# XBee_Shield_v2_0b.net
KiCad netlist of a schematic drawn in EAGLE
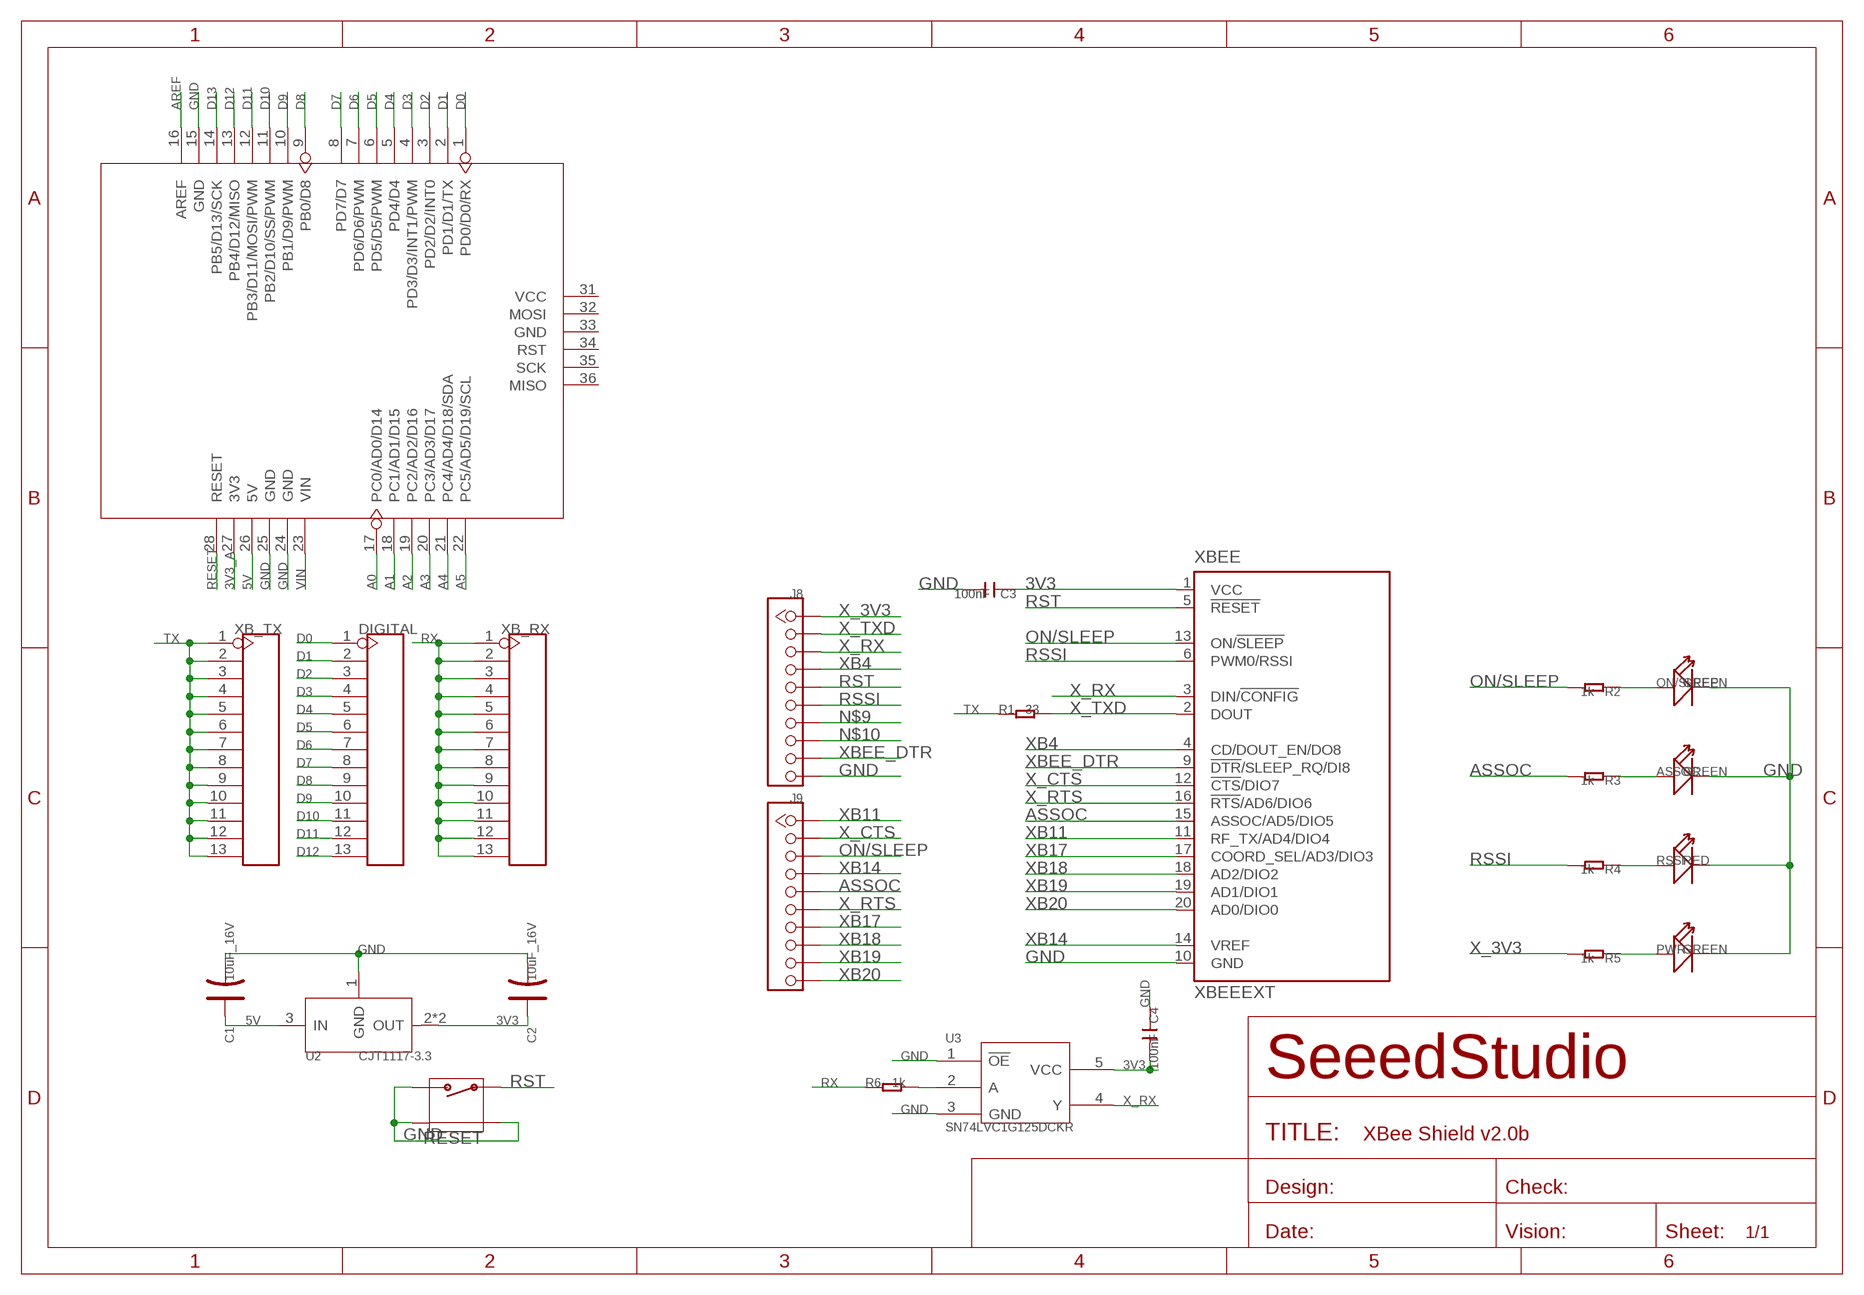
[diagram p0: schematic, sheet 1]

(export (version "E")
  (design (tool "Eeschema 10.0.6"))
  (components
    (comp (ref "ASSOC")
      (value "GREEN")
      (footprint "eagle-import:LED-0603")
      (libsource (lib "eagle-import") (part "LED'0603'"))
    )
    (comp (ref "C1")
      (value "10uF_16V")
      (footprint "eagle-import:AVX-A")
      (libsource (lib "eagle-import") (part "CAP-AVX-A"))
    )
    (comp (ref "C2")
      (value "10uF_16V")
      (footprint "eagle-import:AVX-A")
      (libsource (lib "eagle-import") (part "CAP-AVX-A"))
    )
    (comp (ref "C3")
      (value "100nF")
      (footprint "eagle-import:C0603")
      (libsource (lib "eagle-import") (part "C-0603"))
    )
    (comp (ref "C4")
      (value "100nF")
      (footprint "eagle-import:C0603")
      (libsource (lib "eagle-import") (part "C-0603"))
    )
    (comp (ref "DIGITAL")
      (value "HEADER-13P")
      (footprint "eagle-import:13P-2.54")
      (libsource (lib "eagle-import") (part "HEADER-13P"))
    )
    (comp (ref "J8")
      (value "DNP")
      (footprint "eagle-import:CK1X10")
      (libsource (lib "eagle-import") (part "CK1X10DD"))
    )
    (comp (ref "J9")
      (value "DNP")
      (footprint "eagle-import:CK1X10")
      (libsource (lib "eagle-import") (part "CK1X10DD"))
    )
    (comp (ref "ON/SLEEP")
      (value "GREEN")
      (footprint "eagle-import:LED-0603")
      (libsource (lib "eagle-import") (part "LED'0603'"))
    )
    (comp (ref "PWR")
      (value "GREEN")
      (footprint "eagle-import:LED-0603")
      (libsource (lib "eagle-import") (part "LED'0603'"))
    )
    (comp (ref "R1")
      (value "33")
      (footprint "eagle-import:R0603")
      (libsource (lib "eagle-import") (part "R-0603"))
    )
    (comp (ref "R2")
      (value "1k")
      (footprint "eagle-import:R0603")
      (libsource (lib "eagle-import") (part "R-0603"))
    )
    (comp (ref "R3")
      (value "1k")
      (footprint "eagle-import:R0603")
      (libsource (lib "eagle-import") (part "R-0603"))
    )
    (comp (ref "R4")
      (value "1k")
      (footprint "eagle-import:R0603")
      (libsource (lib "eagle-import") (part "R-0603"))
    )
    (comp (ref "R5")
      (value "1k")
      (footprint "eagle-import:R0603")
      (libsource (lib "eagle-import") (part "R-0603"))
    )
    (comp (ref "R6")
      (value "1k")
      (footprint "eagle-import:R0603")
      (libsource (lib "eagle-import") (part "R-0603"))
    )
    (comp (ref "RESET")
      (value "FOR_TEST_ALBERT_V6_BUTTON_4P_SMD")
      (footprint "eagle-import:FOR_TEST_ALBERT_V6_4P-SMD-7X3.5X3.5")
      (libsource (lib "eagle-import") (part "FOR_TEST_ALBERT_V6_BUTTON_4P_SMD"))
    )
    (comp (ref "RSSI")
      (value "RED")
      (footprint "eagle-import:LED-0603")
      (libsource (lib "eagle-import") (part "LED'0603'"))
    )
    (comp (ref "U1")
      (value "ARDUINO'W/O-SILK'")
      (footprint "eagle-import:ARDUINO-W_O-SILK")
      (libsource (lib "eagle-import") (part "ARDUINO'W/O-SILK'"))
    )
    (comp (ref "U2")
      (value "CJT1117-3.3")
      (footprint "eagle-import:SOT-223")
      (libsource (lib "eagle-import") (part "LD1117S"))
    )
    (comp (ref "U3")
      (value "SN74LVC1G125DCKR")
      (footprint "eagle-import:SOT353")
      (libsource (lib "eagle-import") (part "SN74LVC1G125DCKR"))
    )
    (comp (ref "XBEE")
      (value "XBEEEXT")
      (footprint "eagle-import:XBEE_PLUG")
      (libsource (lib "eagle-import") (part "XBEEEXT"))
    )
    (comp (ref "XB_RX")
      (value "HEADER-13P")
      (footprint "eagle-import:13P-2.54")
      (libsource (lib "eagle-import") (part "HEADER-13P"))
    )
    (comp (ref "XB_TX")
      (value "HEADER-13P")
      (footprint "eagle-import:13P-2.54")
      (libsource (lib "eagle-import") (part "HEADER-13P"))
    )
  )
  (nets
    (net (code "1") (name "/3V3") (class "Default")
      (node (ref "C2") (pin "+") (pinfunction "+_+") (pintype "passive"))
      (node (ref "C3") (pin "1") (pinfunction "1_1") (pintype "passive"))
      (node (ref "C4") (pin "2") (pinfunction "2_2") (pintype "passive"))
      (node (ref "U2") (pin "2") (pinfunction "OUT_2") (pintype "bidirectional"))
      (node (ref "U2") (pin "TER") (pinfunction "OUT_TER") (pintype "bidirectional"))
      (node (ref "U3") (pin "5") (pinfunction "VCC_5") (pintype "bidirectional"))
      (node (ref "XBEE") (pin "1") (pinfunction "VCC_1") (pintype "power_in"))
    )
    (net (code "2") (name "/3V3_A") (class "Default")
      (node (ref "U1") (pin "27") (pinfunction "3V3_27") (pintype "bidirectional"))
    )
    (net (code "3") (name "/5V") (class "Default")
      (node (ref "C1") (pin "+") (pinfunction "+_+") (pintype "passive"))
      (node (ref "U1") (pin "26") (pinfunction "5V_26") (pintype "bidirectional"))
      (node (ref "U2") (pin "3") (pinfunction "IN_3") (pintype "bidirectional"))
    )
    (net (code "4") (name "/A0") (class "Default")
      (node (ref "U1") (pin "17") (pinfunction "PC0/AD0/D14_17") (pintype "bidirectional"))
    )
    (net (code "5") (name "/A1") (class "Default")
      (node (ref "U1") (pin "18") (pinfunction "PC1/AD1/D15_18") (pintype "bidirectional"))
    )
    (net (code "6") (name "/A2") (class "Default")
      (node (ref "U1") (pin "19") (pinfunction "PC2/AD2/D16_19") (pintype "bidirectional"))
    )
    (net (code "7") (name "/A3") (class "Default")
      (node (ref "U1") (pin "20") (pinfunction "PC3/AD3/D17_20") (pintype "bidirectional"))
    )
    (net (code "8") (name "/A4") (class "Default")
      (node (ref "U1") (pin "21") (pinfunction "PC4/AD4/D18/SDA_21") (pintype "bidirectional"))
    )
    (net (code "9") (name "/A5") (class "Default")
      (node (ref "U1") (pin "22") (pinfunction "PC5/AD5/D19/SCL_22") (pintype "bidirectional"))
    )
    (net (code "10") (name "/AREF") (class "Default")
      (node (ref "U1") (pin "16") (pinfunction "AREF_16") (pintype "bidirectional"))
    )
    (net (code "11") (name "/ASSOC") (class "Default")
      (node (ref "J9") (pin "5") (pinfunction "5_5") (pintype "bidirectional"))
      (node (ref "R3") (pin "2") (pinfunction "2_2") (pintype "passive"))
      (node (ref "XBEE") (pin "15") (pinfunction "ASSOC/AD5/DIO5_15") (pintype "bidirectional"))
    )
    (net (code "12") (name "/D0") (class "Default")
      (node (ref "DIGITAL") (pin "1") (pinfunction "1_1") (pintype "bidirectional"))
      (node (ref "U1") (pin "1") (pinfunction "PD0/D0/RX_1") (pintype "bidirectional"))
    )
    (net (code "13") (name "/D1") (class "Default")
      (node (ref "DIGITAL") (pin "2") (pinfunction "2_2") (pintype "bidirectional"))
      (node (ref "U1") (pin "2") (pinfunction "PD1/D1/TX_2") (pintype "bidirectional"))
    )
    (net (code "14") (name "/D2") (class "Default")
      (node (ref "DIGITAL") (pin "3") (pinfunction "3_3") (pintype "bidirectional"))
      (node (ref "U1") (pin "3") (pinfunction "PD2/D2/INT0_3") (pintype "bidirectional"))
    )
    (net (code "15") (name "/D3") (class "Default")
      (node (ref "DIGITAL") (pin "4") (pinfunction "4_4") (pintype "bidirectional"))
      (node (ref "U1") (pin "4") (pinfunction "PD3/D3/INT1/PWM_4") (pintype "bidirectional"))
    )
    (net (code "16") (name "/D4") (class "Default")
      (node (ref "DIGITAL") (pin "5") (pinfunction "5_5") (pintype "bidirectional"))
      (node (ref "U1") (pin "5") (pinfunction "PD4/D4_5") (pintype "bidirectional"))
    )
    (net (code "17") (name "/D5") (class "Default")
      (node (ref "DIGITAL") (pin "6") (pinfunction "6_6") (pintype "bidirectional"))
      (node (ref "U1") (pin "6") (pinfunction "PD5/D5/PWM_6") (pintype "bidirectional"))
    )
    (net (code "18") (name "/D6") (class "Default")
      (node (ref "DIGITAL") (pin "7") (pinfunction "7_7") (pintype "bidirectional"))
      (node (ref "U1") (pin "7") (pinfunction "PD6/D6/PWM_7") (pintype "bidirectional"))
    )
    (net (code "19") (name "/D7") (class "Default")
      (node (ref "DIGITAL") (pin "8") (pinfunction "8_8") (pintype "bidirectional"))
      (node (ref "U1") (pin "8") (pinfunction "PD7/D7_8") (pintype "bidirectional"))
    )
    (net (code "20") (name "/D8") (class "Default")
      (node (ref "DIGITAL") (pin "9") (pinfunction "9_9") (pintype "bidirectional"))
      (node (ref "U1") (pin "9") (pinfunction "PB0/D8_9") (pintype "bidirectional"))
    )
    (net (code "21") (name "/D9") (class "Default")
      (node (ref "DIGITAL") (pin "10") (pinfunction "10_10") (pintype "bidirectional"))
      (node (ref "U1") (pin "10") (pinfunction "PB1/D9/PWM_10") (pintype "bidirectional"))
    )
    (net (code "22") (name "/D10") (class "Default")
      (node (ref "DIGITAL") (pin "11") (pinfunction "11_11") (pintype "bidirectional"))
      (node (ref "U1") (pin "11") (pinfunction "PB2/D10/SS/PWM_11") (pintype "bidirectional"))
    )
    (net (code "23") (name "/D11") (class "Default")
      (node (ref "DIGITAL") (pin "12") (pinfunction "12_12") (pintype "bidirectional"))
      (node (ref "U1") (pin "12") (pinfunction "PB3/D11/MOSI/PWM_12") (pintype "bidirectional"))
    )
    (net (code "24") (name "/D12") (class "Default")
      (node (ref "DIGITAL") (pin "13") (pinfunction "13_13") (pintype "bidirectional"))
      (node (ref "U1") (pin "13") (pinfunction "PB4/D12/MISO_13") (pintype "bidirectional"))
    )
    (net (code "25") (name "/D13") (class "Default")
      (node (ref "U1") (pin "14") (pinfunction "PB5/D13/SCK_14") (pintype "bidirectional"))
    )
    (net (code "26") (name "/GND") (class "Default")
      (node (ref "ASSOC") (pin "-") (pinfunction "-_-") (pintype "passive"))
      (node (ref "C1") (pin "-") (pinfunction "-_-") (pintype "passive"))
      (node (ref "C2") (pin "-") (pinfunction "-_-") (pintype "passive"))
      (node (ref "C3") (pin "2") (pinfunction "2_2") (pintype "passive"))
      (node (ref "C4") (pin "1") (pinfunction "1_1") (pintype "passive"))
      (node (ref "J8") (pin "10") (pinfunction "10_10") (pintype "bidirectional"))
      (node (ref "ON/SLEEP") (pin "-") (pinfunction "-_-") (pintype "passive"))
      (node (ref "PWR") (pin "-") (pinfunction "-_-") (pintype "passive"))
      (node (ref "RESET") (pin "2") (pinfunction "2_2") (pintype "bidirectional"))
      (node (ref "RESET") (pin "S1") (pinfunction "S1_S1") (pintype "bidirectional"))
      (node (ref "RESET") (pin "S2") (pinfunction "S2_S2") (pintype "bidirectional"))
      (node (ref "RSSI") (pin "-") (pinfunction "-_-") (pintype "passive"))
      (node (ref "U1") (pin "15") (pinfunction "GND_15") (pintype "bidirectional"))
      (node (ref "U1") (pin "24") (pinfunction "GND_24") (pintype "bidirectional"))
      (node (ref "U1") (pin "25") (pinfunction "GND_25") (pintype "bidirectional"))
      (node (ref "U2") (pin "1") (pinfunction "GND_1") (pintype "bidirectional"))
      (node (ref "U3") (pin "1") (pinfunction "~{OE}_1") (pintype "bidirectional"))
      (node (ref "U3") (pin "3") (pinfunction "GND_3") (pintype "bidirectional"))
      (node (ref "XBEE") (pin "10") (pinfunction "GND_10") (pintype "bidirectional"))
    )
    (net (code "27") (name "/N$9") (class "Default")
      (node (ref "J8") (pin "7") (pinfunction "7_7") (pintype "bidirectional"))
    )
    (net (code "28") (name "/N$10") (class "Default")
      (node (ref "J8") (pin "8") (pinfunction "8_8") (pintype "bidirectional"))
    )
    (net (code "29") (name "/ON{slash}SLEEP") (class "Default")
      (node (ref "J9") (pin "3") (pinfunction "3_3") (pintype "bidirectional"))
      (node (ref "R2") (pin "2") (pinfunction "2_2") (pintype "passive"))
      (node (ref "XBEE") (pin "13") (pinfunction "ON/~{SLEEP}_13") (pintype "output"))
    )
    (net (code "30") (name "/RESET") (class "Default")
      (node (ref "U1") (pin "28") (pinfunction "RESET_28") (pintype "bidirectional"))
    )
    (net (code "31") (name "/RSSI") (class "Default")
      (node (ref "J8") (pin "6") (pinfunction "6_6") (pintype "bidirectional"))
      (node (ref "R4") (pin "2") (pinfunction "2_2") (pintype "passive"))
      (node (ref "XBEE") (pin "6") (pinfunction "PWM0/RSSI_6") (pintype "output"))
    )
    (net (code "32") (name "/RST") (class "Default")
      (node (ref "J8") (pin "5") (pinfunction "5_5") (pintype "bidirectional"))
      (node (ref "RESET") (pin "1") (pinfunction "1_1") (pintype "bidirectional"))
      (node (ref "XBEE") (pin "5") (pinfunction "~{RESET}_5") (pintype "input"))
    )
    (net (code "33") (name "/RX") (class "Default")
      (node (ref "R6") (pin "1") (pinfunction "1_1") (pintype "passive"))
      (node (ref "XB_RX") (pin "1") (pinfunction "1_1") (pintype "bidirectional"))
      (node (ref "XB_RX") (pin "10") (pinfunction "10_10") (pintype "bidirectional"))
      (node (ref "XB_RX") (pin "11") (pinfunction "11_11") (pintype "bidirectional"))
      (node (ref "XB_RX") (pin "12") (pinfunction "12_12") (pintype "bidirectional"))
      (node (ref "XB_RX") (pin "13") (pinfunction "13_13") (pintype "bidirectional"))
      (node (ref "XB_RX") (pin "2") (pinfunction "2_2") (pintype "bidirectional"))
      (node (ref "XB_RX") (pin "3") (pinfunction "3_3") (pintype "bidirectional"))
      (node (ref "XB_RX") (pin "4") (pinfunction "4_4") (pintype "bidirectional"))
      (node (ref "XB_RX") (pin "5") (pinfunction "5_5") (pintype "bidirectional"))
      (node (ref "XB_RX") (pin "6") (pinfunction "6_6") (pintype "bidirectional"))
      (node (ref "XB_RX") (pin "7") (pinfunction "7_7") (pintype "bidirectional"))
      (node (ref "XB_RX") (pin "8") (pinfunction "8_8") (pintype "bidirectional"))
      (node (ref "XB_RX") (pin "9") (pinfunction "9_9") (pintype "bidirectional"))
    )
    (net (code "34") (name "/TX") (class "Default")
      (node (ref "R1") (pin "1") (pinfunction "1_1") (pintype "passive"))
      (node (ref "XB_TX") (pin "1") (pinfunction "1_1") (pintype "bidirectional"))
      (node (ref "XB_TX") (pin "10") (pinfunction "10_10") (pintype "bidirectional"))
      (node (ref "XB_TX") (pin "11") (pinfunction "11_11") (pintype "bidirectional"))
      (node (ref "XB_TX") (pin "12") (pinfunction "12_12") (pintype "bidirectional"))
      (node (ref "XB_TX") (pin "13") (pinfunction "13_13") (pintype "bidirectional"))
      (node (ref "XB_TX") (pin "2") (pinfunction "2_2") (pintype "bidirectional"))
      (node (ref "XB_TX") (pin "3") (pinfunction "3_3") (pintype "bidirectional"))
      (node (ref "XB_TX") (pin "4") (pinfunction "4_4") (pintype "bidirectional"))
      (node (ref "XB_TX") (pin "5") (pinfunction "5_5") (pintype "bidirectional"))
      (node (ref "XB_TX") (pin "6") (pinfunction "6_6") (pintype "bidirectional"))
      (node (ref "XB_TX") (pin "7") (pinfunction "7_7") (pintype "bidirectional"))
      (node (ref "XB_TX") (pin "8") (pinfunction "8_8") (pintype "bidirectional"))
      (node (ref "XB_TX") (pin "9") (pinfunction "9_9") (pintype "bidirectional"))
    )
    (net (code "35") (name "/VIN") (class "Default")
      (node (ref "U1") (pin "23") (pinfunction "VIN_23") (pintype "bidirectional"))
    )
    (net (code "36") (name "/XB4") (class "Default")
      (node (ref "J8") (pin "4") (pinfunction "4_4") (pintype "bidirectional"))
      (node (ref "XBEE") (pin "4") (pinfunction "CD/DOUT_EN/DO8_4") (pintype "output"))
    )
    (net (code "37") (name "/XB11") (class "Default")
      (node (ref "J9") (pin "1") (pinfunction "1_1") (pintype "bidirectional"))
      (node (ref "XBEE") (pin "11") (pinfunction "RF_TX/AD4/DIO4_11") (pintype "bidirectional"))
    )
    (net (code "38") (name "/XB14") (class "Default")
      (node (ref "J9") (pin "4") (pinfunction "4_4") (pintype "bidirectional"))
      (node (ref "XBEE") (pin "14") (pinfunction "VREF_14") (pintype "input"))
    )
    (net (code "39") (name "/XB17") (class "Default")
      (node (ref "J9") (pin "7") (pinfunction "7_7") (pintype "bidirectional"))
      (node (ref "XBEE") (pin "17") (pinfunction "COORD_SEL/AD3/DIO3_17") (pintype "bidirectional"))
    )
    (net (code "40") (name "/XB18") (class "Default")
      (node (ref "J9") (pin "8") (pinfunction "8_8") (pintype "bidirectional"))
      (node (ref "XBEE") (pin "18") (pinfunction "AD2/DIO2_18") (pintype "bidirectional"))
    )
    (net (code "41") (name "/XB19") (class "Default")
      (node (ref "J9") (pin "9") (pinfunction "9_9") (pintype "bidirectional"))
      (node (ref "XBEE") (pin "19") (pinfunction "AD1/DIO1_19") (pintype "bidirectional"))
    )
    (net (code "42") (name "/XB20") (class "Default")
      (node (ref "J9") (pin "10") (pinfunction "10_10") (pintype "bidirectional"))
      (node (ref "XBEE") (pin "20") (pinfunction "AD0/DIO0_20") (pintype "bidirectional"))
    )
    (net (code "43") (name "/XBEE_DTR") (class "Default")
      (node (ref "J8") (pin "9") (pinfunction "9_9") (pintype "bidirectional"))
      (node (ref "XBEE") (pin "9") (pinfunction "~{DTR}/SLEEP_RQ/DI8_9") (pintype "bidirectional"))
    )
    (net (code "44") (name "/X_3V3") (class "Default")
      (node (ref "J8") (pin "1") (pinfunction "1_1") (pintype "bidirectional"))
      (node (ref "R5") (pin "2") (pinfunction "2_2") (pintype "passive"))
    )
    (net (code "45") (name "/X_CTS") (class "Default")
      (node (ref "J9") (pin "2") (pinfunction "2_2") (pintype "bidirectional"))
      (node (ref "XBEE") (pin "12") (pinfunction "~{CTS}/DIO7_12") (pintype "bidirectional"))
    )
    (net (code "46") (name "/X_RTS") (class "Default")
      (node (ref "J9") (pin "6") (pinfunction "6_6") (pintype "bidirectional"))
      (node (ref "XBEE") (pin "16") (pinfunction "~{RTS}/AD6/DIO6_16") (pintype "bidirectional"))
    )
    (net (code "47") (name "/X_RX") (class "Default")
      (node (ref "J8") (pin "3") (pinfunction "3_3") (pintype "bidirectional"))
      (node (ref "U3") (pin "4") (pinfunction "Y_4") (pintype "bidirectional"))
      (node (ref "XBEE") (pin "3") (pinfunction "DIN/~{CONFIG}_3") (pintype "input"))
    )
    (net (code "48") (name "/X_TXD") (class "Default")
      (node (ref "J8") (pin "2") (pinfunction "2_2") (pintype "bidirectional"))
      (node (ref "R1") (pin "2") (pinfunction "2_2") (pintype "passive"))
      (node (ref "XBEE") (pin "2") (pinfunction "DOUT_2") (pintype "output"))
    )
    (net (code "49") (name "Net-(ASSOC-Pad+)") (class "Default")
      (node (ref "ASSOC") (pin "+") (pinfunction "+_+") (pintype "passive"))
      (node (ref "R3") (pin "1") (pinfunction "1_1") (pintype "passive"))
    )
    (net (code "50") (name "Net-(ON/SLEEP-Pad+)") (class "Default")
      (node (ref "ON/SLEEP") (pin "+") (pinfunction "+_+") (pintype "passive"))
      (node (ref "R2") (pin "1") (pinfunction "1_1") (pintype "passive"))
    )
    (net (code "51") (name "Net-(PWR-Pad+)") (class "Default")
      (node (ref "PWR") (pin "+") (pinfunction "+_+") (pintype "passive"))
      (node (ref "R5") (pin "1") (pinfunction "1_1") (pintype "passive"))
    )
    (net (code "52") (name "Net-(R4-Pad1)") (class "Default")
      (node (ref "R4") (pin "1") (pinfunction "1_1") (pintype "passive"))
      (node (ref "RSSI") (pin "+") (pinfunction "+_+") (pintype "passive"))
    )
    (net (code "53") (name "Net-(U3-A)") (class "Default")
      (node (ref "R6") (pin "2") (pinfunction "2_2") (pintype "passive"))
      (node (ref "U3") (pin "2") (pinfunction "A_2") (pintype "bidirectional"))
    )
    (net (code "54") (name "unconnected-(U1-GND-Pad33)") (class "Default")
      (node (ref "U1") (pin "33") (pinfunction "GND_33") (pintype "bidirectional"))
    )
    (net (code "55") (name "unconnected-(U1-MISO-Pad36)") (class "Default")
      (node (ref "U1") (pin "36") (pinfunction "MISO_36") (pintype "bidirectional"))
    )
    (net (code "56") (name "unconnected-(U1-MOSI-Pad32)") (class "Default")
      (node (ref "U1") (pin "32") (pinfunction "MOSI_32") (pintype "bidirectional"))
    )
    (net (code "57") (name "unconnected-(U1-RST-Pad34)") (class "Default")
      (node (ref "U1") (pin "34") (pinfunction "RST_34") (pintype "bidirectional"))
    )
    (net (code "58") (name "unconnected-(U1-SCK-Pad35)") (class "Default")
      (node (ref "U1") (pin "35") (pinfunction "SCK_35") (pintype "bidirectional"))
    )
    (net (code "59") (name "unconnected-(U1-VCC-Pad31)") (class "Default")
      (node (ref "U1") (pin "31") (pinfunction "VCC_31") (pintype "bidirectional"))
    )
  )
)
